# couch-pwr-rb.net
KiCad netlist of a schematic drawn in EAGLE
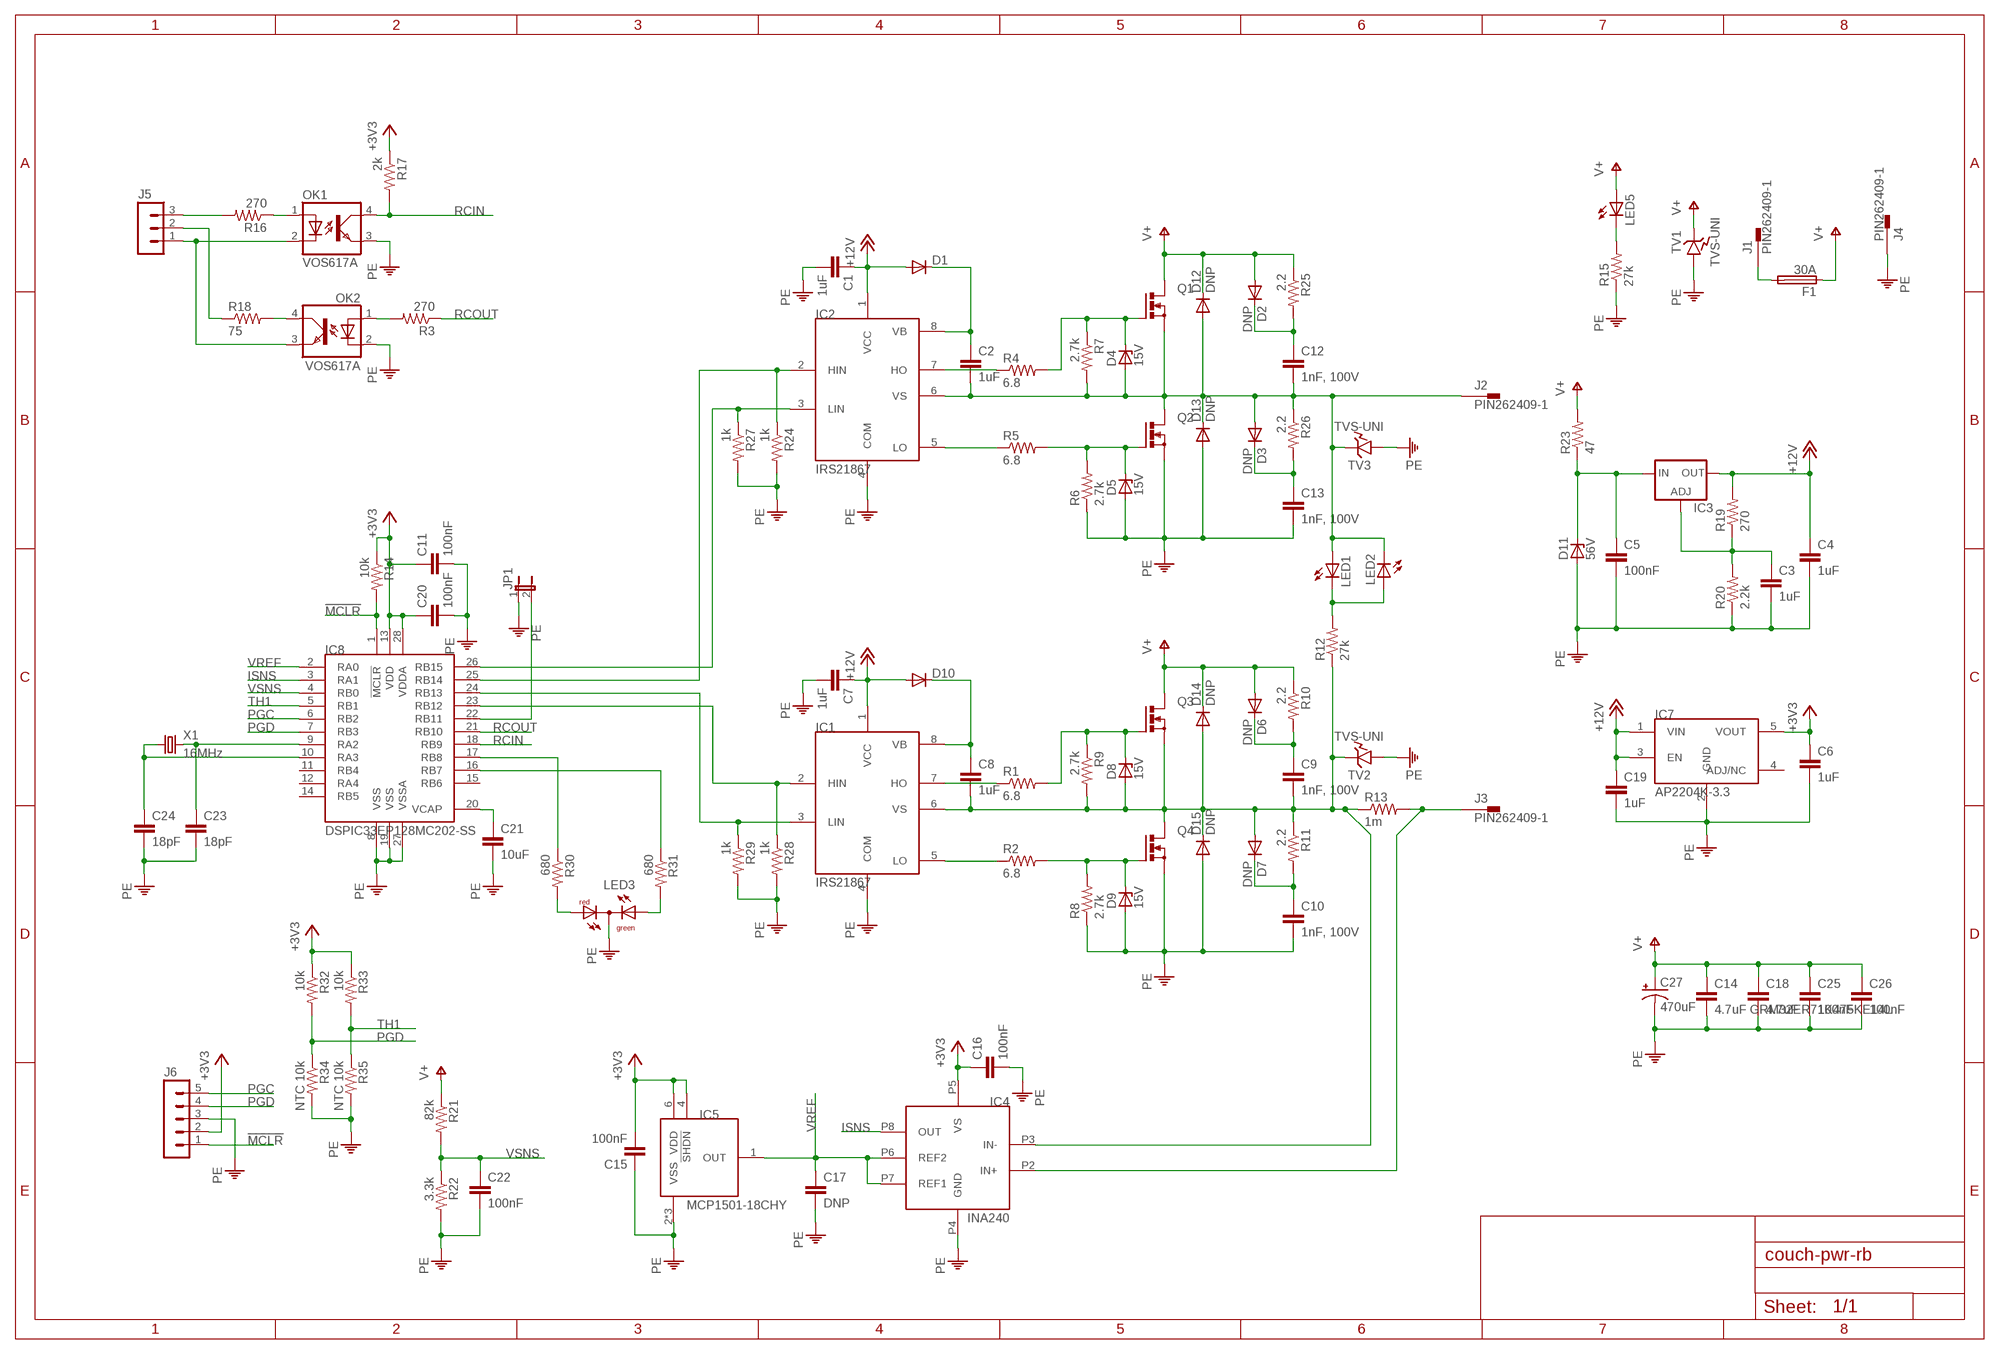
[diagram p0: schematic, sheet 1]

(export (version "E")
  (design (tool "Eeschema 10.0.6"))
  (components
    (comp (ref "C1")
      (value "1uF")
      (footprint "eagle-import:C0805")
      (libsource (lib "eagle-import") (part "C-EUC0805"))
    )
    (comp (ref "C2")
      (value "1uF")
      (footprint "eagle-import:C0805")
      (libsource (lib "eagle-import") (part "C-EUC0805"))
    )
    (comp (ref "C3")
      (value "1uF")
      (footprint "eagle-import:C0805")
      (libsource (lib "eagle-import") (part "C-EUC0805"))
    )
    (comp (ref "C4")
      (value "1uF")
      (footprint "eagle-import:C0805")
      (libsource (lib "eagle-import") (part "C-EUC0805"))
    )
    (comp (ref "C5")
      (value "100nF")
      (footprint "eagle-import:C0805")
      (libsource (lib "eagle-import") (part "C-EUC0805"))
    )
    (comp (ref "C6")
      (value "1uF")
      (footprint "eagle-import:C0603")
      (libsource (lib "eagle-import") (part "C-EUC0603"))
    )
    (comp (ref "C7")
      (value "1uF")
      (footprint "eagle-import:C0805")
      (libsource (lib "eagle-import") (part "C-EUC0805"))
    )
    (comp (ref "C8")
      (value "1uF")
      (footprint "eagle-import:C0805")
      (libsource (lib "eagle-import") (part "C-EUC0805"))
    )
    (comp (ref "C9")
      (value "1nF, 100V")
      (footprint "eagle-import:C1206")
      (libsource (lib "eagle-import") (part "C-EUC1206"))
    )
    (comp (ref "C10")
      (value "1nF, 100V")
      (footprint "eagle-import:C1206")
      (libsource (lib "eagle-import") (part "C-EUC1206"))
    )
    (comp (ref "C11")
      (value "100nF")
      (footprint "eagle-import:C0603")
      (libsource (lib "eagle-import") (part "C-EUC0603"))
    )
    (comp (ref "C12")
      (value "1nF, 100V")
      (footprint "eagle-import:C1206")
      (libsource (lib "eagle-import") (part "C-EUC1206"))
    )
    (comp (ref "C13")
      (value "1nF, 100V")
      (footprint "eagle-import:C1206")
      (libsource (lib "eagle-import") (part "C-EUC1206"))
    )
    (comp (ref "C14")
      (value "4.7uF GRM32ER71K475KE14L")
      (footprint "eagle-import:C1210")
      (libsource (lib "eagle-import") (part "C-EUC1210"))
    )
    (comp (ref "C15")
      (value "100nF")
      (footprint "eagle-import:C0603")
      (libsource (lib "eagle-import") (part "C-EUC0603"))
    )
    (comp (ref "C16")
      (value "100nF")
      (footprint "eagle-import:C0603")
      (libsource (lib "eagle-import") (part "C-EUC0603"))
    )
    (comp (ref "C17")
      (value "DNP")
      (footprint "eagle-import:C0603")
      (libsource (lib "eagle-import") (part "C-EUC0603"))
    )
    (comp (ref "C18")
      (value "4.7uF")
      (footprint "eagle-import:C1210")
      (libsource (lib "eagle-import") (part "C-EUC1210"))
    )
    (comp (ref "C19")
      (value "1uF")
      (footprint "eagle-import:C0603")
      (libsource (lib "eagle-import") (part "C-EUC0603"))
    )
    (comp (ref "C20")
      (value "100nF")
      (footprint "eagle-import:C0603")
      (libsource (lib "eagle-import") (part "C-EUC0603"))
    )
    (comp (ref "C21")
      (value "10uF")
      (footprint "eagle-import:C0603")
      (libsource (lib "eagle-import") (part "C-EUC0603"))
    )
    (comp (ref "C22")
      (value "100nF")
      (footprint "eagle-import:C0603")
      (libsource (lib "eagle-import") (part "C-EUC0603"))
    )
    (comp (ref "C23")
      (value "18pF")
      (footprint "eagle-import:C0603")
      (libsource (lib "eagle-import") (part "C-EUC0603"))
    )
    (comp (ref "C24")
      (value "18pF")
      (footprint "eagle-import:C0603")
      (libsource (lib "eagle-import") (part "C-EUC0603"))
    )
    (comp (ref "C25")
      (value "100nF")
      (footprint "eagle-import:C1206")
      (libsource (lib "eagle-import") (part "C-EUC1206"))
    )
    (comp (ref "C26")
      (value "100nF")
      (footprint "eagle-import:C1206")
      (libsource (lib "eagle-import") (part "C-EUC1206"))
    )
    (comp (ref "C27")
      (value "470uF")
      (footprint "eagle-import:E7,5-16")
      (libsource (lib "eagle-import") (part "CPOL-USE7.5-16"))
    )
    (comp (ref "D1")
      (value "DIODE-SOD323-W")
      (footprint "eagle-import:SOD323-W")
      (libsource (lib "eagle-import") (part "DIODE-SOD323-W"))
    )
    (comp (ref "D2")
      (value "DNP")
      (footprint "eagle-import:DO-214AC")
      (libsource (lib "eagle-import") (part "DIODE-DO-214AC"))
    )
    (comp (ref "D3")
      (value "DNP")
      (footprint "eagle-import:DO-214AC")
      (libsource (lib "eagle-import") (part "DIODE-DO-214AC"))
    )
    (comp (ref "D4")
      (value "15V")
      (footprint "eagle-import:SOD80C")
      (libsource (lib "eagle-import") (part "ZENER-DIODESOD80C"))
    )
    (comp (ref "D5")
      (value "15V")
      (footprint "eagle-import:SOD80C")
      (libsource (lib "eagle-import") (part "ZENER-DIODESOD80C"))
    )
    (comp (ref "D6")
      (value "DNP")
      (footprint "eagle-import:DO-214AC")
      (libsource (lib "eagle-import") (part "DIODE-DO-214AC"))
    )
    (comp (ref "D7")
      (value "DNP")
      (footprint "eagle-import:DO-214AC")
      (libsource (lib "eagle-import") (part "DIODE-DO-214AC"))
    )
    (comp (ref "D8")
      (value "15V")
      (footprint "eagle-import:SOD80C")
      (libsource (lib "eagle-import") (part "ZENER-DIODESOD80C"))
    )
    (comp (ref "D9")
      (value "15V")
      (footprint "eagle-import:SOD80C")
      (libsource (lib "eagle-import") (part "ZENER-DIODESOD80C"))
    )
    (comp (ref "D10")
      (value "DIODE-SOD323-W")
      (footprint "eagle-import:SOD323-W")
      (libsource (lib "eagle-import") (part "DIODE-SOD323-W"))
    )
    (comp (ref "D11")
      (value "56V")
      (footprint "eagle-import:SMB")
      (libsource (lib "eagle-import") (part "ZENER-DIODESMB"))
    )
    (comp (ref "D12")
      (value "DNP")
      (footprint "eagle-import:SMC")
      (libsource (lib "eagle-import") (part "DIODE-SMC"))
    )
    (comp (ref "D13")
      (value "DNP")
      (footprint "eagle-import:SMC")
      (libsource (lib "eagle-import") (part "DIODE-SMC"))
    )
    (comp (ref "D14")
      (value "DNP")
      (footprint "eagle-import:SMC")
      (libsource (lib "eagle-import") (part "DIODE-SMC"))
    )
    (comp (ref "D15")
      (value "DNP")
      (footprint "eagle-import:SMC")
      (libsource (lib "eagle-import") (part "DIODE-SMC"))
    )
    (comp (ref "F1")
      (value "30A")
      (footprint "eagle-import:BLADEFUSE")
      (libsource (lib "eagle-import") (part "FUSEBLADE"))
    )
    (comp (ref "IC1")
      (value "IRS21867")
      (footprint "eagle-import:SO-08")
      (libsource (lib "eagle-import") (part "IRS21867"))
    )
    (comp (ref "IC2")
      (value "IRS21867")
      (footprint "eagle-import:SO-08")
      (libsource (lib "eagle-import") (part "IRS21867"))
    )
    (comp (ref "IC3")
      (value "LM317TLBH")
      (footprint "eagle-import:TO220BH")
      (libsource (lib "eagle-import") (part "LM317TLBH"))
    )
    (comp (ref "IC4")
      (value "INA240")
      (footprint "eagle-import:VSSOP-8")
      (libsource (lib "eagle-import") (part "INA240"))
    )
    (comp (ref "IC5")
      (value "MCP1501-18CHY")
      (footprint "eagle-import:SOT23-6")
      (libsource (lib "eagle-import") (part "MCP1501-CHY18"))
    )
    (comp (ref "IC7")
      (value "AP2204K-3.3")
      (footprint "eagle-import:SOT23-5")
      (libsource (lib "eagle-import") (part "AP2204K-5.0"))
    )
    (comp (ref "IC8")
      (value "DSPIC33EP128MC202-SS")
      (footprint "eagle-import:SSOP-28")
      (libsource (lib "eagle-import") (part "DSPIC33EPMC202-SS128"))
    )
    (comp (ref "J1")
      (value "PIN262409-1")
      (footprint "eagle-import:62409-1")
      (libsource (lib "eagle-import") (part "PIN262409-1"))
    )
    (comp (ref "J2")
      (value "PIN262409-1")
      (footprint "eagle-import:62409-1")
      (libsource (lib "eagle-import") (part "PIN262409-1"))
    )
    (comp (ref "J3")
      (value "PIN262409-1")
      (footprint "eagle-import:62409-1")
      (libsource (lib "eagle-import") (part "PIN262409-1"))
    )
    (comp (ref "J4")
      (value "PIN262409-1")
      (footprint "eagle-import:62409-1")
      (libsource (lib "eagle-import") (part "PIN262409-1"))
    )
    (comp (ref "J5")
      (value "MA03-1")
      (footprint "eagle-import:MA03-1")
      (libsource (lib "eagle-import") (part "MA03-1"))
    )
    (comp (ref "J6")
      (value "MA05-1")
      (footprint "eagle-import:MA05-1")
      (libsource (lib "eagle-import") (part "MA05-1"))
    )
    (comp (ref "JP1")
      (value "JP1E")
      (footprint "eagle-import:JP1")
      (libsource (lib "eagle-import") (part "JP1E"))
    )
    (comp (ref "LED1")
      (value "LEDCHIP-LED0603")
      (footprint "eagle-import:CHIP-LED0603")
      (libsource (lib "eagle-import") (part "LEDCHIP-LED0603"))
    )
    (comp (ref "LED2")
      (value "LEDCHIP-LED0603")
      (footprint "eagle-import:CHIP-LED0603")
      (libsource (lib "eagle-import") (part "LEDCHIP-LED0603"))
    )
    (comp (ref "LED3")
      (value "DUOLED-RG-C")
      (footprint "eagle-import:DUOLED-C-5MM")
      (libsource (lib "eagle-import") (part "DUOLED-RG-C"))
    )
    (comp (ref "LED5")
      (value "LEDCHIP-LED0603")
      (footprint "eagle-import:CHIP-LED0603")
      (libsource (lib "eagle-import") (part "LEDCHIP-LED0603"))
    )
    (comp (ref "OK1")
      (value "VOS617A")
      (footprint "eagle-import:MINI-FLAT-4")
      (libsource (lib "eagle-import") (part "TLP283"))
    )
    (comp (ref "OK2")
      (value "VOS617A")
      (footprint "eagle-import:MINI-FLAT-4")
      (libsource (lib "eagle-import") (part "TLP283"))
    )
    (comp (ref "Q1")
      (value "PMOSFET_NTO220BH")
      (footprint "eagle-import:TO220BH")
      (libsource (lib "eagle-import") (part "PMOSFET_NTO220BH"))
    )
    (comp (ref "Q2")
      (value "PMOSFET_NTO220BH")
      (footprint "eagle-import:TO220BH")
      (libsource (lib "eagle-import") (part "PMOSFET_NTO220BH"))
    )
    (comp (ref "Q3")
      (value "PMOSFET_NTO220BH")
      (footprint "eagle-import:TO220BH")
      (libsource (lib "eagle-import") (part "PMOSFET_NTO220BH"))
    )
    (comp (ref "Q4")
      (value "PMOSFET_NTO220BH")
      (footprint "eagle-import:TO220BH")
      (libsource (lib "eagle-import") (part "PMOSFET_NTO220BH"))
    )
    (comp (ref "R1")
      (value "6.8")
      (footprint "eagle-import:R1206")
      (libsource (lib "eagle-import") (part "R-US_R1206"))
    )
    (comp (ref "R2")
      (value "6.8")
      (footprint "eagle-import:R1206")
      (libsource (lib "eagle-import") (part "R-US_R1206"))
    )
    (comp (ref "R3")
      (value "270")
      (footprint "eagle-import:R0603")
      (libsource (lib "eagle-import") (part "R-US_R0603"))
    )
    (comp (ref "R4")
      (value "6.8")
      (footprint "eagle-import:R1206")
      (libsource (lib "eagle-import") (part "R-US_R1206"))
    )
    (comp (ref "R5")
      (value "6.8")
      (footprint "eagle-import:R1206")
      (libsource (lib "eagle-import") (part "R-US_R1206"))
    )
    (comp (ref "R6")
      (value "2.7k")
      (footprint "eagle-import:R0603")
      (libsource (lib "eagle-import") (part "R-US_R0603"))
    )
    (comp (ref "R7")
      (value "2.7k")
      (footprint "eagle-import:R0603")
      (libsource (lib "eagle-import") (part "R-US_R0603"))
    )
    (comp (ref "R8")
      (value "2.7k")
      (footprint "eagle-import:R0603")
      (libsource (lib "eagle-import") (part "R-US_R0603"))
    )
    (comp (ref "R9")
      (value "2.7k")
      (footprint "eagle-import:R0603")
      (libsource (lib "eagle-import") (part "R-US_R0603"))
    )
    (comp (ref "R10")
      (value "2.2")
      (footprint "eagle-import:R1206")
      (libsource (lib "eagle-import") (part "R-US_R1206"))
    )
    (comp (ref "R11")
      (value "2.2")
      (footprint "eagle-import:R1206")
      (libsource (lib "eagle-import") (part "R-US_R1206"))
    )
    (comp (ref "R12")
      (value "27k")
      (footprint "eagle-import:R0603")
      (libsource (lib "eagle-import") (part "R-US_R0603"))
    )
    (comp (ref "R13")
      (value "1m")
      (footprint "eagle-import:R2512")
      (libsource (lib "eagle-import") (part "R-US_R2512"))
    )
    (comp (ref "R14")
      (value "10k")
      (footprint "eagle-import:R0603")
      (libsource (lib "eagle-import") (part "R-US_R0603"))
    )
    (comp (ref "R15")
      (value "27k")
      (footprint "eagle-import:R0603")
      (libsource (lib "eagle-import") (part "R-US_R0603"))
    )
    (comp (ref "R16")
      (value "270")
      (footprint "eagle-import:R0603")
      (libsource (lib "eagle-import") (part "R-US_R0603"))
    )
    (comp (ref "R17")
      (value "2k")
      (footprint "eagle-import:R0603")
      (libsource (lib "eagle-import") (part "R-US_R0603"))
    )
    (comp (ref "R18")
      (value "75")
      (footprint "eagle-import:R0603")
      (libsource (lib "eagle-import") (part "R-US_R0603"))
    )
    (comp (ref "R19")
      (value "270")
      (footprint "eagle-import:R0603")
      (libsource (lib "eagle-import") (part "R-US_R0603"))
    )
    (comp (ref "R20")
      (value "2.2k")
      (footprint "eagle-import:R0603")
      (libsource (lib "eagle-import") (part "R-US_R0603"))
    )
    (comp (ref "R21")
      (value "82k")
      (footprint "eagle-import:R0603")
      (libsource (lib "eagle-import") (part "R-US_R0603"))
    )
    (comp (ref "R22")
      (value "3.3k")
      (footprint "eagle-import:R0603")
      (libsource (lib "eagle-import") (part "R-US_R0603"))
    )
    (comp (ref "R23")
      (value "47")
      (footprint "eagle-import:R1206")
      (libsource (lib "eagle-import") (part "R-US_R1206"))
    )
    (comp (ref "R24")
      (value "1k")
      (footprint "eagle-import:R0603")
      (libsource (lib "eagle-import") (part "R-US_R0603"))
    )
    (comp (ref "R25")
      (value "2.2")
      (footprint "eagle-import:R1206")
      (libsource (lib "eagle-import") (part "R-US_R1206"))
    )
    (comp (ref "R26")
      (value "2.2")
      (footprint "eagle-import:R1206")
      (libsource (lib "eagle-import") (part "R-US_R1206"))
    )
    (comp (ref "R27")
      (value "1k")
      (footprint "eagle-import:R0603")
      (libsource (lib "eagle-import") (part "R-US_R0603"))
    )
    (comp (ref "R28")
      (value "1k")
      (footprint "eagle-import:R0603")
      (libsource (lib "eagle-import") (part "R-US_R0603"))
    )
    (comp (ref "R29")
      (value "1k")
      (footprint "eagle-import:R0603")
      (libsource (lib "eagle-import") (part "R-US_R0603"))
    )
    (comp (ref "R30")
      (value "680")
      (footprint "eagle-import:R0603")
      (libsource (lib "eagle-import") (part "R-US_R0603"))
    )
    (comp (ref "R31")
      (value "680")
      (footprint "eagle-import:R0603")
      (libsource (lib "eagle-import") (part "R-US_R0603"))
    )
    (comp (ref "R32")
      (value "10k")
      (footprint "eagle-import:R0603")
      (libsource (lib "eagle-import") (part "R-US_R0603"))
    )
    (comp (ref "R33")
      (value "10k")
      (footprint "eagle-import:R0603")
      (libsource (lib "eagle-import") (part "R-US_R0603"))
    )
    (comp (ref "R34")
      (value "NTC 10k")
      (footprint "eagle-import:R0603")
      (libsource (lib "eagle-import") (part "R-US_R0603"))
    )
    (comp (ref "R35")
      (value "NTC 10k")
      (footprint "eagle-import:R0603")
      (libsource (lib "eagle-import") (part "R-US_R0603"))
    )
    (comp (ref "TV1")
      (value "TVS-UNI")
      (footprint "eagle-import:SMC")
      (libsource (lib "eagle-import") (part "TVS-UNI"))
    )
    (comp (ref "TV2")
      (value "TVS-UNI")
      (footprint "eagle-import:SMC")
      (libsource (lib "eagle-import") (part "TVS-UNI"))
    )
    (comp (ref "TV3")
      (value "TVS-UNI")
      (footprint "eagle-import:SMC")
      (libsource (lib "eagle-import") (part "TVS-UNI"))
    )
    (comp (ref "X1")
      (value "16MHz")
      (footprint "eagle-import:HC49_S")
      (libsource (lib "eagle-import") (part "CRYSTALHC49S"))
    )
  )
  (nets
    (net (code "1") (name "+3V3") (class "Default")
      (node (ref "C11") (pin "1") (pinfunction "1_1") (pintype "passive"))
      (node (ref "C15") (pin "2") (pinfunction "2_2") (pintype "passive"))
      (node (ref "C16") (pin "1") (pinfunction "1_1") (pintype "passive"))
      (node (ref "C20") (pin "1") (pinfunction "1_1") (pintype "passive"))
      (node (ref "C6") (pin "1") (pinfunction "1_1") (pintype "passive"))
      (node (ref "IC4") (pin "P5") (pinfunction "VS_P5") (pintype "power_in"))
      (node (ref "IC5") (pin "4") (pinfunction "~{SHDN}_4") (pintype "input"))
      (node (ref "IC5") (pin "6") (pinfunction "VDD_6") (pintype "power_in"))
      (node (ref "IC7") (pin "5") (pinfunction "VOUT_5") (pintype "power_in"))
      (node (ref "IC8") (pin "13") (pinfunction "VDD_13") (pintype "power_in"))
      (node (ref "IC8") (pin "28") (pinfunction "VDDA_28") (pintype "power_in"))
      (node (ref "J6") (pin "2") (pinfunction "2_2") (pintype "passive"))
      (node (ref "R14") (pin "1") (pinfunction "1_1") (pintype "passive"))
      (node (ref "R17") (pin "1") (pinfunction "1_1") (pintype "passive"))
      (node (ref "R32") (pin "1") (pinfunction "1_1") (pintype "passive"))
      (node (ref "R33") (pin "1") (pinfunction "1_1") (pintype "passive"))
    )
    (net (code "2") (name "+12V") (class "Default")
      (node (ref "C1") (pin "1") (pinfunction "1_1") (pintype "passive"))
      (node (ref "C19") (pin "1") (pinfunction "1_1") (pintype "passive"))
      (node (ref "C4") (pin "1") (pinfunction "1_1") (pintype "passive"))
      (node (ref "C7") (pin "1") (pinfunction "1_1") (pintype "passive"))
      (node (ref "D1") (pin "A") (pinfunction "A_A") (pintype "passive"))
      (node (ref "D10") (pin "A") (pinfunction "A_A") (pintype "passive"))
      (node (ref "IC1") (pin "1") (pinfunction "VCC_1") (pintype "power_in"))
      (node (ref "IC2") (pin "1") (pinfunction "VCC_1") (pintype "power_in"))
      (node (ref "IC3") (pin "D") (pinfunction "OUT_D") (pintype "passive"))
      (node (ref "IC7") (pin "1") (pinfunction "VIN_1") (pintype "power_in"))
      (node (ref "IC7") (pin "3") (pinfunction "EN_3") (pintype "input"))
      (node (ref "R19") (pin "2") (pinfunction "2_2") (pintype "passive"))
    )
    (net (code "3") (name "/ISNS") (class "Default")
      (node (ref "IC4") (pin "P8") (pinfunction "OUT_P8") (pintype "output"))
      (node (ref "IC8") (pin "3") (pinfunction "RA1_3") (pintype "bidirectional"))
    )
    (net (code "4") (name "/PGC") (class "Default")
      (node (ref "IC8") (pin "6") (pinfunction "RB2_6") (pintype "bidirectional"))
      (node (ref "J6") (pin "5") (pinfunction "5_5") (pintype "passive"))
    )
    (net (code "5") (name "/PGD") (class "Default")
      (node (ref "IC8") (pin "7") (pinfunction "RB3_7") (pintype "bidirectional"))
      (node (ref "J6") (pin "4") (pinfunction "4_4") (pintype "passive"))
      (node (ref "R32") (pin "2") (pinfunction "2_2") (pintype "passive"))
      (node (ref "R34") (pin "1") (pinfunction "1_1") (pintype "passive"))
    )
    (net (code "6") (name "/RCIN") (class "Default")
      (node (ref "IC8") (pin "18") (pinfunction "RB9_18") (pintype "bidirectional"))
      (node (ref "OK1") (pin "4") (pinfunction "COL_4") (pintype "passive"))
      (node (ref "R17") (pin "2") (pinfunction "2_2") (pintype "passive"))
    )
    (net (code "7") (name "/RCOUT") (class "Default")
      (node (ref "IC8") (pin "21") (pinfunction "RB10_21") (pintype "bidirectional"))
      (node (ref "R3") (pin "1") (pinfunction "1_1") (pintype "passive"))
    )
    (net (code "8") (name "/TH1") (class "Default")
      (node (ref "IC8") (pin "5") (pinfunction "RB1_5") (pintype "bidirectional"))
      (node (ref "R33") (pin "2") (pinfunction "2_2") (pintype "passive"))
      (node (ref "R35") (pin "1") (pinfunction "1_1") (pintype "passive"))
    )
    (net (code "9") (name "/VREF") (class "Default")
      (node (ref "C17") (pin "1") (pinfunction "1_1") (pintype "passive"))
      (node (ref "IC4") (pin "P6") (pinfunction "REF2_P6") (pintype "passive"))
      (node (ref "IC4") (pin "P7") (pinfunction "REF1_P7") (pintype "passive"))
      (node (ref "IC5") (pin "1") (pinfunction "OUT_1") (pintype "output"))
      (node (ref "IC8") (pin "2") (pinfunction "RA0_2") (pintype "bidirectional"))
    )
    (net (code "10") (name "/VSNS") (class "Default")
      (node (ref "C22") (pin "1") (pinfunction "1_1") (pintype "passive"))
      (node (ref "IC8") (pin "4") (pinfunction "RB0_4") (pintype "bidirectional"))
      (node (ref "R21") (pin "2") (pinfunction "2_2") (pintype "passive"))
      (node (ref "R22") (pin "1") (pinfunction "1_1") (pintype "passive"))
    )
    (net (code "11") (name "/~{MCLR}") (class "Default")
      (node (ref "IC8") (pin "1") (pinfunction "~{MCLR}_1") (pintype "input"))
      (node (ref "J6") (pin "1") (pinfunction "1_1") (pintype "passive"))
      (node (ref "R14") (pin "2") (pinfunction "2_2") (pintype "passive"))
    )
    (net (code "12") (name "Net-(C9-Pad1)") (class "Default")
      (node (ref "C9") (pin "1") (pinfunction "1_1") (pintype "passive"))
      (node (ref "D6") (pin "C") (pinfunction "C_C") (pintype "passive"))
      (node (ref "R10") (pin "2") (pinfunction "2_2") (pintype "passive"))
    )
    (net (code "13") (name "Net-(C10-Pad1)") (class "Default")
      (node (ref "C10") (pin "1") (pinfunction "1_1") (pintype "passive"))
      (node (ref "D7") (pin "C") (pinfunction "C_C") (pintype "passive"))
      (node (ref "R11") (pin "2") (pinfunction "2_2") (pintype "passive"))
    )
    (net (code "14") (name "Net-(C12-Pad1)") (class "Default")
      (node (ref "C12") (pin "1") (pinfunction "1_1") (pintype "passive"))
      (node (ref "D2") (pin "C") (pinfunction "C_C") (pintype "passive"))
      (node (ref "R25") (pin "2") (pinfunction "2_2") (pintype "passive"))
    )
    (net (code "15") (name "Net-(C13-Pad1)") (class "Default")
      (node (ref "C13") (pin "1") (pinfunction "1_1") (pintype "passive"))
      (node (ref "D3") (pin "C") (pinfunction "C_C") (pintype "passive"))
      (node (ref "R26") (pin "2") (pinfunction "2_2") (pintype "passive"))
    )
    (net (code "16") (name "Net-(D4-PadC)") (class "Default")
      (node (ref "D4") (pin "C") (pinfunction "C_C") (pintype "passive"))
      (node (ref "Q1") (pin "G") (pinfunction "G_G") (pintype "passive"))
      (node (ref "R4") (pin "2") (pinfunction "2_2") (pintype "passive"))
      (node (ref "R7") (pin "1") (pinfunction "1_1") (pintype "passive"))
    )
    (net (code "17") (name "Net-(D5-PadC)") (class "Default")
      (node (ref "D5") (pin "C") (pinfunction "C_C") (pintype "passive"))
      (node (ref "Q2") (pin "G") (pinfunction "G_G") (pintype "passive"))
      (node (ref "R5") (pin "2") (pinfunction "2_2") (pintype "passive"))
      (node (ref "R6") (pin "2") (pinfunction "2_2") (pintype "passive"))
    )
    (net (code "18") (name "Net-(D8-PadC)") (class "Default")
      (node (ref "D8") (pin "C") (pinfunction "C_C") (pintype "passive"))
      (node (ref "Q3") (pin "G") (pinfunction "G_G") (pintype "passive"))
      (node (ref "R1") (pin "2") (pinfunction "2_2") (pintype "passive"))
      (node (ref "R9") (pin "1") (pinfunction "1_1") (pintype "passive"))
    )
    (net (code "19") (name "Net-(D9-PadC)") (class "Default")
      (node (ref "D9") (pin "C") (pinfunction "C_C") (pintype "passive"))
      (node (ref "Q4") (pin "G") (pinfunction "G_G") (pintype "passive"))
      (node (ref "R2") (pin "2") (pinfunction "2_2") (pintype "passive"))
      (node (ref "R8") (pin "2") (pinfunction "2_2") (pintype "passive"))
    )
    (net (code "20") (name "Net-(F1-2-Pad2A)") (class "Default")
      (node (ref "F1") (pin "2A") (pinfunction "2_2A") (pintype "passive"))
      (node (ref "F1") (pin "2B") (pinfunction "2_2B") (pintype "passive"))
      (node (ref "J1") (pin "A1") (pinfunction "1_A1") (pintype "passive"))
      (node (ref "J1") (pin "A2") (pinfunction "1_A2") (pintype "passive"))
    )
    (net (code "21") (name "Net-(IC1-HIN)") (class "Default")
      (node (ref "IC1") (pin "2") (pinfunction "HIN_2") (pintype "input"))
      (node (ref "IC8") (pin "23") (pinfunction "RB12_23") (pintype "bidirectional"))
      (node (ref "R28") (pin "1") (pinfunction "1_1") (pintype "passive"))
    )
    (net (code "22") (name "Net-(IC1-HO)") (class "Default")
      (node (ref "IC1") (pin "7") (pinfunction "HO_7") (pintype "output"))
      (node (ref "R1") (pin "1") (pinfunction "1_1") (pintype "passive"))
    )
    (net (code "23") (name "Net-(IC1-LIN)") (class "Default")
      (node (ref "IC1") (pin "3") (pinfunction "LIN_3") (pintype "input"))
      (node (ref "IC8") (pin "24") (pinfunction "RB13_24") (pintype "bidirectional"))
      (node (ref "R29") (pin "1") (pinfunction "1_1") (pintype "passive"))
    )
    (net (code "24") (name "Net-(IC1-LO)") (class "Default")
      (node (ref "IC1") (pin "5") (pinfunction "LO_5") (pintype "output"))
      (node (ref "R2") (pin "1") (pinfunction "1_1") (pintype "passive"))
    )
    (net (code "25") (name "Net-(IC1-VB)") (class "Default")
      (node (ref "C8") (pin "1") (pinfunction "1_1") (pintype "passive"))
      (node (ref "D10") (pin "C") (pinfunction "C_C") (pintype "passive"))
      (node (ref "IC1") (pin "8") (pinfunction "VB_8") (pintype "passive"))
    )
    (net (code "26") (name "Net-(IC1-VS)") (class "Default")
      (node (ref "C8") (pin "2") (pinfunction "2_2") (pintype "passive"))
      (node (ref "C9") (pin "2") (pinfunction "2_2") (pintype "passive"))
      (node (ref "D14") (pin "A") (pinfunction "A_A") (pintype "passive"))
      (node (ref "D15") (pin "C") (pinfunction "C_C") (pintype "passive"))
      (node (ref "D7") (pin "A") (pinfunction "A_A") (pintype "passive"))
      (node (ref "D8") (pin "A") (pinfunction "A_A") (pintype "passive"))
      (node (ref "IC1") (pin "6") (pinfunction "VS_6") (pintype "passive"))
      (node (ref "IC4") (pin "P3") (pinfunction "IN-_P3") (pintype "input"))
      (node (ref "Q3") (pin "S") (pinfunction "S_S") (pintype "passive"))
      (node (ref "Q4") (pin "D") (pinfunction "D_D") (pintype "passive"))
      (node (ref "R11") (pin "1") (pinfunction "1_1") (pintype "passive"))
      (node (ref "R12") (pin "1") (pinfunction "1_1") (pintype "passive"))
      (node (ref "R13") (pin "1") (pinfunction "1_1") (pintype "passive"))
      (node (ref "R9") (pin "2") (pinfunction "2_2") (pintype "passive"))
      (node (ref "TV2") (pin "1") (pinfunction "M1_1") (pintype "passive"))
    )
    (net (code "27") (name "Net-(IC2-HIN)") (class "Default")
      (node (ref "IC2") (pin "2") (pinfunction "HIN_2") (pintype "input"))
      (node (ref "IC8") (pin "25") (pinfunction "RB14_25") (pintype "bidirectional"))
      (node (ref "R24") (pin "1") (pinfunction "1_1") (pintype "passive"))
    )
    (net (code "28") (name "Net-(IC2-HO)") (class "Default")
      (node (ref "IC2") (pin "7") (pinfunction "HO_7") (pintype "output"))
      (node (ref "R4") (pin "1") (pinfunction "1_1") (pintype "passive"))
    )
    (net (code "29") (name "Net-(IC2-LIN)") (class "Default")
      (node (ref "IC2") (pin "3") (pinfunction "LIN_3") (pintype "input"))
      (node (ref "IC8") (pin "26") (pinfunction "RB15_26") (pintype "bidirectional"))
      (node (ref "R27") (pin "1") (pinfunction "1_1") (pintype "passive"))
    )
    (net (code "30") (name "Net-(IC2-LO)") (class "Default")
      (node (ref "IC2") (pin "5") (pinfunction "LO_5") (pintype "output"))
      (node (ref "R5") (pin "1") (pinfunction "1_1") (pintype "passive"))
    )
    (net (code "31") (name "Net-(IC2-VB)") (class "Default")
      (node (ref "C2") (pin "1") (pinfunction "1_1") (pintype "passive"))
      (node (ref "D1") (pin "C") (pinfunction "C_C") (pintype "passive"))
      (node (ref "IC2") (pin "8") (pinfunction "VB_8") (pintype "passive"))
    )
    (net (code "32") (name "Net-(IC2-VS)") (class "Default")
      (node (ref "C12") (pin "2") (pinfunction "2_2") (pintype "passive"))
      (node (ref "C2") (pin "2") (pinfunction "2_2") (pintype "passive"))
      (node (ref "D12") (pin "A") (pinfunction "A_A") (pintype "passive"))
      (node (ref "D13") (pin "C") (pinfunction "C_C") (pintype "passive"))
      (node (ref "D3") (pin "A") (pinfunction "A_A") (pintype "passive"))
      (node (ref "D4") (pin "A") (pinfunction "A_A") (pintype "passive"))
      (node (ref "IC2") (pin "6") (pinfunction "VS_6") (pintype "passive"))
      (node (ref "J2") (pin "A1") (pinfunction "1_A1") (pintype "passive"))
      (node (ref "J2") (pin "A2") (pinfunction "1_A2") (pintype "passive"))
      (node (ref "LED1") (pin "A") (pinfunction "A_A") (pintype "passive"))
      (node (ref "LED2") (pin "C") (pinfunction "C_C") (pintype "passive"))
      (node (ref "Q1") (pin "S") (pinfunction "S_S") (pintype "passive"))
      (node (ref "Q2") (pin "D") (pinfunction "D_D") (pintype "passive"))
      (node (ref "R26") (pin "1") (pinfunction "1_1") (pintype "passive"))
      (node (ref "R7") (pin "2") (pinfunction "2_2") (pintype "passive"))
      (node (ref "TV3") (pin "1") (pinfunction "M1_1") (pintype "passive"))
    )
    (net (code "33") (name "Net-(IC3-ADJ)") (class "Default")
      (node (ref "C3") (pin "1") (pinfunction "1_1") (pintype "passive"))
      (node (ref "IC3") (pin "G") (pinfunction "ADJ_G") (pintype "input"))
      (node (ref "R19") (pin "1") (pinfunction "1_1") (pintype "passive"))
      (node (ref "R20") (pin "2") (pinfunction "2_2") (pintype "passive"))
    )
    (net (code "34") (name "Net-(IC3-IN)") (class "Default")
      (node (ref "C5") (pin "1") (pinfunction "1_1") (pintype "passive"))
      (node (ref "D11") (pin "C") (pinfunction "C_C") (pintype "passive"))
      (node (ref "IC3") (pin "S") (pinfunction "IN_S") (pintype "input"))
      (node (ref "R23") (pin "1") (pinfunction "1_1") (pintype "passive"))
    )
    (net (code "35") (name "Net-(IC4-IN+)") (class "Default")
      (node (ref "IC4") (pin "P2") (pinfunction "IN+_P2") (pintype "input"))
      (node (ref "J3") (pin "A1") (pinfunction "1_A1") (pintype "passive"))
      (node (ref "J3") (pin "A2") (pinfunction "1_A2") (pintype "passive"))
      (node (ref "R13") (pin "2") (pinfunction "2_2") (pintype "passive"))
    )
    (net (code "36") (name "Net-(IC8-RA2)") (class "Default")
      (node (ref "C23") (pin "1") (pinfunction "1_1") (pintype "passive"))
      (node (ref "IC8") (pin "9") (pinfunction "RA2_9") (pintype "bidirectional"))
      (node (ref "X1") (pin "2") (pinfunction "2_2") (pintype "passive"))
    )
    (net (code "37") (name "Net-(IC8-RA3)") (class "Default")
      (node (ref "C24") (pin "1") (pinfunction "1_1") (pintype "passive"))
      (node (ref "IC8") (pin "10") (pinfunction "RA3_10") (pintype "bidirectional"))
      (node (ref "X1") (pin "1") (pinfunction "1_1") (pintype "passive"))
    )
    (net (code "38") (name "Net-(IC8-RB7)") (class "Default")
      (node (ref "IC8") (pin "16") (pinfunction "RB7_16") (pintype "bidirectional"))
      (node (ref "R31") (pin "1") (pinfunction "1_1") (pintype "passive"))
    )
    (net (code "39") (name "Net-(IC8-RB8)") (class "Default")
      (node (ref "IC8") (pin "17") (pinfunction "RB8_17") (pintype "bidirectional"))
      (node (ref "R30") (pin "1") (pinfunction "1_1") (pintype "passive"))
    )
    (net (code "40") (name "Net-(IC8-RB11)") (class "Default")
      (node (ref "IC8") (pin "22") (pinfunction "RB11_22") (pintype "bidirectional"))
      (node (ref "JP1") (pin "2") (pinfunction "2_2") (pintype "passive"))
    )
    (net (code "41") (name "Net-(IC8-VCAP)") (class "Default")
      (node (ref "C21") (pin "1") (pinfunction "1_1") (pintype "passive"))
      (node (ref "IC8") (pin "20") (pinfunction "VCAP_20") (pintype "passive"))
    )
    (net (code "42") (name "Net-(J5-Pad2)") (class "Default")
      (node (ref "J5") (pin "2") (pinfunction "2_2") (pintype "passive"))
      (node (ref "R18") (pin "1") (pinfunction "1_1") (pintype "passive"))
    )
    (net (code "43") (name "Net-(J5-Pad3)") (class "Default")
      (node (ref "J5") (pin "3") (pinfunction "3_3") (pintype "passive"))
      (node (ref "R16") (pin "2") (pinfunction "2_2") (pintype "passive"))
    )
    (net (code "44") (name "Net-(LED1-PadC)") (class "Default")
      (node (ref "LED1") (pin "C") (pinfunction "C_C") (pintype "passive"))
      (node (ref "LED2") (pin "A") (pinfunction "A_A") (pintype "passive"))
      (node (ref "R12") (pin "2") (pinfunction "2_2") (pintype "passive"))
    )
    (net (code "45") (name "Net-(LED3-AG)") (class "Default")
      (node (ref "LED3") (pin "AX") (pinfunction "AG_AX") (pintype "passive"))
      (node (ref "R31") (pin "2") (pinfunction "2_2") (pintype "passive"))
    )
    (net (code "46") (name "Net-(LED3-PadAR)") (class "Default")
      (node (ref "LED3") (pin "AR") (pinfunction "AR_AR") (pintype "passive"))
      (node (ref "R30") (pin "2") (pinfunction "2_2") (pintype "passive"))
    )
    (net (code "47") (name "Net-(LED5-PadC)") (class "Default")
      (node (ref "LED5") (pin "C") (pinfunction "C_C") (pintype "passive"))
      (node (ref "R15") (pin "2") (pinfunction "2_2") (pintype "passive"))
    )
    (net (code "48") (name "Net-(OK1-A)") (class "Default")
      (node (ref "OK1") (pin "1") (pinfunction "A_1") (pintype "passive"))
      (node (ref "R16") (pin "1") (pinfunction "1_1") (pintype "passive"))
    )
    (net (code "49") (name "Net-(OK1-C)") (class "Default")
      (node (ref "J5") (pin "1") (pinfunction "1_1") (pintype "passive"))
      (node (ref "OK1") (pin "2") (pinfunction "C_2") (pintype "passive"))
      (node (ref "OK2") (pin "3") (pinfunction "EMIT_3") (pintype "passive"))
    )
    (net (code "50") (name "Net-(OK2-A)") (class "Default")
      (node (ref "OK2") (pin "1") (pinfunction "A_1") (pintype "passive"))
      (node (ref "R3") (pin "2") (pinfunction "2_2") (pintype "passive"))
    )
    (net (code "51") (name "Net-(OK2-COL)") (class "Default")
      (node (ref "OK2") (pin "4") (pinfunction "COL_4") (pintype "passive"))
      (node (ref "R18") (pin "2") (pinfunction "2_2") (pintype "passive"))
    )
    (net (code "52") (name "PE") (class "Default")
      (node (ref "C1") (pin "2") (pinfunction "2_2") (pintype "passive"))
      (node (ref "C10") (pin "2") (pinfunction "2_2") (pintype "passive"))
      (node (ref "C11") (pin "2") (pinfunction "2_2") (pintype "passive"))
      (node (ref "C13") (pin "2") (pinfunction "2_2") (pintype "passive"))
      (node (ref "C14") (pin "2") (pinfunction "2_2") (pintype "passive"))
      (node (ref "C15") (pin "1") (pinfunction "1_1") (pintype "passive"))
      (node (ref "C16") (pin "2") (pinfunction "2_2") (pintype "passive"))
      (node (ref "C17") (pin "2") (pinfunction "2_2") (pintype "passive"))
      (node (ref "C18") (pin "2") (pinfunction "2_2") (pintype "passive"))
      (node (ref "C19") (pin "2") (pinfunction "2_2") (pintype "passive"))
      (node (ref "C20") (pin "2") (pinfunction "2_2") (pintype "passive"))
      (node (ref "C21") (pin "2") (pinfunction "2_2") (pintype "passive"))
      (node (ref "C22") (pin "2") (pinfunction "2_2") (pintype "passive"))
      (node (ref "C23") (pin "2") (pinfunction "2_2") (pintype "passive"))
      (node (ref "C24") (pin "2") (pinfunction "2_2") (pintype "passive"))
      (node (ref "C25") (pin "2") (pinfunction "2_2") (pintype "passive"))
      (node (ref "C26") (pin "2") (pinfunction "2_2") (pintype "passive"))
      (node (ref "C27") (pin "-") (pinfunction "-_-") (pintype "passive"))
      (node (ref "C3") (pin "2") (pinfunction "2_2") (pintype "passive"))
      (node (ref "C4") (pin "2") (pinfunction "2_2") (pintype "passive"))
      (node (ref "C5") (pin "2") (pinfunction "2_2") (pintype "passive"))
      (node (ref "C6") (pin "2") (pinfunction "2_2") (pintype "passive"))
      (node (ref "C7") (pin "2") (pinfunction "2_2") (pintype "passive"))
      (node (ref "D11") (pin "A") (pinfunction "A_A") (pintype "passive"))
      (node (ref "D13") (pin "A") (pinfunction "A_A") (pintype "passive"))
      (node (ref "D15") (pin "A") (pinfunction "A_A") (pintype "passive"))
      (node (ref "D5") (pin "A") (pinfunction "A_A") (pintype "passive"))
      (node (ref "D9") (pin "A") (pinfunction "A_A") (pintype "passive"))
      (node (ref "IC1") (pin "4") (pinfunction "COM_4") (pintype "power_in"))
      (node (ref "IC2") (pin "4") (pinfunction "COM_4") (pintype "power_in"))
      (node (ref "IC4") (pin "P4") (pinfunction "GND_P4") (pintype "power_in"))
      (node (ref "IC5") (pin "2") (pinfunction "VSS_2") (pintype "power_in"))
      (node (ref "IC5") (pin "3") (pinfunction "VSS_3") (pintype "power_in"))
      (node (ref "IC5") (pin "5") (pinfunction "VSS_5") (pintype "power_in"))
      (node (ref "IC7") (pin "2") (pinfunction "GND_2") (pintype "power_in"))
      (node (ref "IC8") (pin "19") (pinfunction "VSS_19") (pintype "power_in"))
      (node (ref "IC8") (pin "27") (pinfunction "VSSA_27") (pintype "power_in"))
      (node (ref "IC8") (pin "8") (pinfunction "VSS_8") (pintype "power_in"))
      (node (ref "J4") (pin "A1") (pinfunction "1_A1") (pintype "passive"))
      (node (ref "J4") (pin "A2") (pinfunction "1_A2") (pintype "passive"))
      (node (ref "J6") (pin "3") (pinfunction "3_3") (pintype "passive"))
      (node (ref "JP1") (pin "1") (pinfunction "1_1") (pintype "passive"))
      (node (ref "LED3") (pin "C") (pinfunction "C_C") (pintype "passive"))
      (node (ref "OK1") (pin "3") (pinfunction "EMIT_3") (pintype "passive"))
      (node (ref "OK2") (pin "2") (pinfunction "C_2") (pintype "passive"))
      (node (ref "Q2") (pin "S") (pinfunction "S_S") (pintype "passive"))
      (node (ref "Q4") (pin "S") (pinfunction "S_S") (pintype "passive"))
      (node (ref "R15") (pin "1") (pinfunction "1_1") (pintype "passive"))
      (node (ref "R20") (pin "1") (pinfunction "1_1") (pintype "passive"))
      (node (ref "R22") (pin "2") (pinfunction "2_2") (pintype "passive"))
      (node (ref "R24") (pin "2") (pinfunction "2_2") (pintype "passive"))
      (node (ref "R27") (pin "2") (pinfunction "2_2") (pintype "passive"))
      (node (ref "R28") (pin "2") (pinfunction "2_2") (pintype "passive"))
      (node (ref "R29") (pin "2") (pinfunction "2_2") (pintype "passive"))
      (node (ref "R34") (pin "2") (pinfunction "2_2") (pintype "passive"))
      (node (ref "R35") (pin "2") (pinfunction "2_2") (pintype "passive"))
      (node (ref "R6") (pin "1") (pinfunction "1_1") (pintype "passive"))
      (node (ref "R8") (pin "1") (pinfunction "1_1") (pintype "passive"))
      (node (ref "TV1") (pin "2") (pinfunction "M2_2") (pintype "passive"))
      (node (ref "TV2") (pin "2") (pinfunction "M2_2") (pintype "passive"))
      (node (ref "TV3") (pin "2") (pinfunction "M2_2") (pintype "passive"))
    )
    (net (code "53") (name "V+") (class "Default")
      (node (ref "C14") (pin "1") (pinfunction "1_1") (pintype "passive"))
      (node (ref "C18") (pin "1") (pinfunction "1_1") (pintype "passive"))
      (node (ref "C25") (pin "1") (pinfunction "1_1") (pintype "passive"))
      (node (ref "C26") (pin "1") (pinfunction "1_1") (pintype "passive"))
      (node (ref "C27") (pin "+") (pinfunction "+_+") (pintype "passive"))
      (node (ref "D12") (pin "C") (pinfunction "C_C") (pintype "passive"))
      (node (ref "D14") (pin "C") (pinfunction "C_C") (pintype "passive"))
      (node (ref "D2") (pin "A") (pinfunction "A_A") (pintype "passive"))
      (node (ref "D6") (pin "A") (pinfunction "A_A") (pintype "passive"))
      (node (ref "F1") (pin "1A") (pinfunction "1_1A") (pintype "passive"))
      (node (ref "F1") (pin "1B") (pinfunction "1_1B") (pintype "passive"))
      (node (ref "LED5") (pin "A") (pinfunction "A_A") (pintype "passive"))
      (node (ref "Q1") (pin "D") (pinfunction "D_D") (pintype "passive"))
      (node (ref "Q3") (pin "D") (pinfunction "D_D") (pintype "passive"))
      (node (ref "R10") (pin "1") (pinfunction "1_1") (pintype "passive"))
      (node (ref "R21") (pin "1") (pinfunction "1_1") (pintype "passive"))
      (node (ref "R23") (pin "2") (pinfunction "2_2") (pintype "passive"))
      (node (ref "R25") (pin "1") (pinfunction "1_1") (pintype "passive"))
      (node (ref "TV1") (pin "1") (pinfunction "M1_1") (pintype "passive"))
    )
    (net (code "54") (name "unconnected-(IC7-ADJ{slash}NC-Pad4)") (class "Default")
      (node (ref "IC7") (pin "4") (pinfunction "ADJ/NC_4") (pintype "input"))
    )
    (net (code "55") (name "unconnected-(IC8-RA4-Pad12)") (class "Default")
      (node (ref "IC8") (pin "12") (pinfunction "RA4_12") (pintype "bidirectional"))
    )
    (net (code "56") (name "unconnected-(IC8-RB4-Pad11)") (class "Default")
      (node (ref "IC8") (pin "11") (pinfunction "RB4_11") (pintype "bidirectional"))
    )
    (net (code "57") (name "unconnected-(IC8-RB5-Pad14)") (class "Default")
      (node (ref "IC8") (pin "14") (pinfunction "RB5_14") (pintype "bidirectional"))
    )
    (net (code "58") (name "unconnected-(IC8-RB6-Pad15)") (class "Default")
      (node (ref "IC8") (pin "15") (pinfunction "RB6_15") (pintype "bidirectional"))
    )
  )
)
